# Display_System_sch.net
KiCad netlist of a schematic drawn in Altium Designer
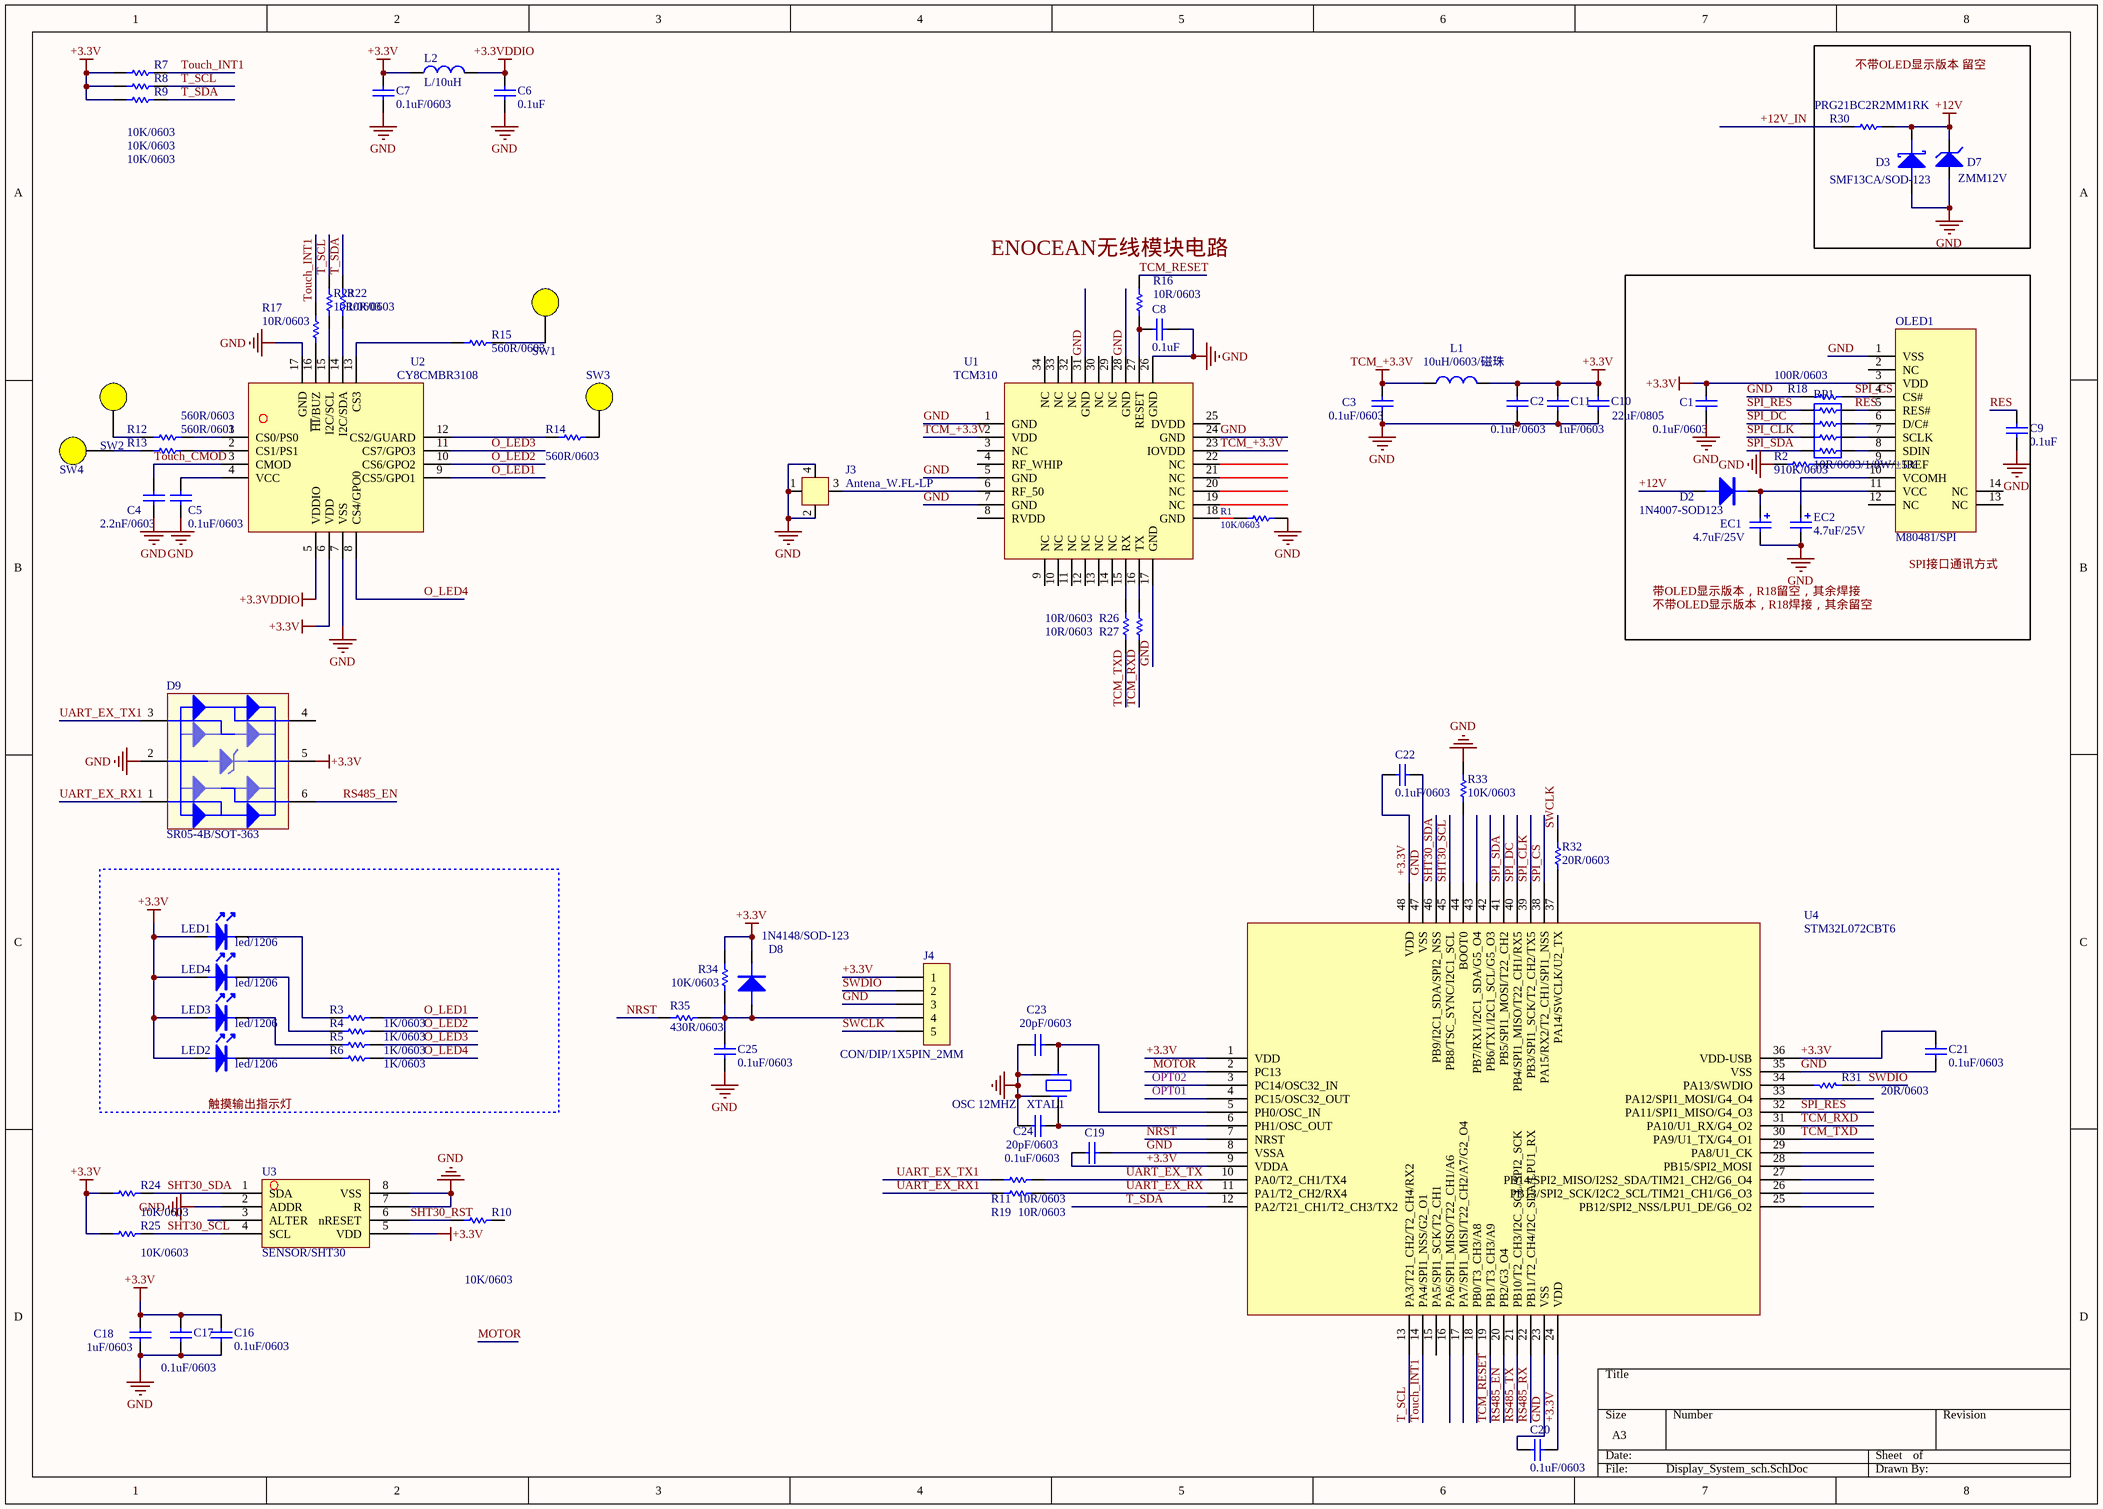
[diagram p0: Display_System_sch.SchDoc]

(export (version "E")
  (design (tool "Eeschema 10.0.6"))
  (components
    (comp (ref "C1")
      (value "0.1uF/0603")
      (footprint "CAP/SMT/0603C")
      (libsource (lib "Menred_原理图 封装库") (part "CAP/CAP/SMT/0603C"))
    )
    (comp (ref "C2")
      (value "0.1uF/0603")
      (footprint "CAP/SMT/0603C")
      (libsource (lib "Menred_原理图 封装库") (part "CAP/CAP/SMT/0603C"))
    )
    (comp (ref "C3")
      (value "0.1uF/0603")
      (footprint "CAP/SMT/0603C")
      (libsource (lib "Menred_原理图 封装库") (part "CAP/CAP/SMT/0603C"))
    )
    (comp (ref "C4")
      (value "2.2nF/0603")
      (footprint "CAP/SMT/0603C")
      (libsource (lib "Menred_原理图 封装库") (part "CAP/CAP/SMT/0603C"))
    )
    (comp (ref "C5")
      (value "0.1uF/0603")
      (footprint "CAP/SMT/0603C")
      (libsource (lib "Menred_原理图 封装库") (part "CAP/CAP/SMT/0603C"))
    )
    (comp (ref "C6")
      (value "0.1uF")
      (footprint "CAP/SMT/0603C")
      (libsource (lib "Menred_原理图 封装库") (part "CAP/CAP/SMT/0603C"))
    )
    (comp (ref "C7")
      (value "0.1uF/0603")
      (footprint "CAP/SMT/0603C")
      (libsource (lib "Menred_原理图 封装库") (part "CAP/CAP/SMT/0603C"))
    )
    (comp (ref "C8")
      (value "0.1uF")
      (footprint "CAP/SMT/0603C")
      (libsource (lib "") (part "CAP/CAP/SMT/0603C_1"))
    )
    (comp (ref "C9")
      (value "0.1uF")
      (footprint "CAP/SMT/0603C")
      (libsource (lib "Menred_原理图 封装库") (part "CAP/CAP/SMT/0603C"))
    )
    (comp (ref "C10")
      (value "22uF/0805")
      (footprint "CAP/SMT/0805C")
      (libsource (lib "Menred_原理图 封装库") (part "CAP/CAP/SMT/0805C"))
    )
    (comp (ref "C11")
      (value "1uF/0603")
      (footprint "CAP/SMT/0603C")
      (libsource (lib "Menred_原理图 封装库") (part "CAP/CAP/SMT/0603C"))
    )
    (comp (ref "C16")
      (value "0.1uF/0603")
      (footprint "CAP/SMT/0603C")
      (libsource (lib "Menred_原理图 封装库") (part "CAP/CAP/SMT/0603C"))
    )
    (comp (ref "C17")
      (value "0.1uF/0603")
      (footprint "CAP/SMT/0603C")
      (libsource (lib "Menred_原理图 封装库") (part "CAP/CAP/SMT/0603C"))
    )
    (comp (ref "C18")
      (value "1uF/0603")
      (footprint "CAP/SMT/0603C")
      (libsource (lib "Menred_原理图 封装库") (part "CAP/CAP/SMT/0603C"))
    )
    (comp (ref "C19")
      (value "0.1uF/0603")
      (footprint "CAP/SMT/0603C")
      (libsource (lib "Menred_原理图 封装库") (part "CAP/CAP/SMT/0603C"))
    )
    (comp (ref "C20")
      (value "0.1uF/0603")
      (footprint "CAP/SMT/0603C")
      (libsource (lib "Menred_原理图 封装库") (part "CAP/CAP/SMT/0603C"))
    )
    (comp (ref "C21")
      (value "0.1uF/0603")
      (footprint "CAP/SMT/0603C")
      (libsource (lib "Menred_原理图 封装库") (part "CAP/CAP/SMT/0603C"))
    )
    (comp (ref "C22")
      (value "0.1uF/0603")
      (footprint "CAP/SMT/0603C")
      (libsource (lib "Menred_原理图 封装库") (part "CAP/CAP/SMT/0603C"))
    )
    (comp (ref "C23")
      (value "20pF/0603")
      (footprint "CAP/SMT/0603C")
      (libsource (lib "Menred_原理图 封装库") (part "CAP/CAP/SMT/0603C"))
    )
    (comp (ref "C24")
      (value "20pF/0603")
      (footprint "CAP/SMT/0603C")
      (libsource (lib "Menred_原理图 封装库") (part "CAP/CAP/SMT/0603C"))
    )
    (comp (ref "C25")
      (value "0.1uF/0603")
      (footprint "CAP/SMT/0603C")
      (libsource (lib "Menred_原理图 封装库") (part "CAP/CAP/SMT/0603C"))
    )
    (comp (ref "D2")
      (value "1N4007-SOD123")
      (footprint "D/SMT/SOD123")
      (libsource (lib "Menred_原理图 封装库") (part "D/D/SMT/1N4007-SOD123"))
    )
    (comp (ref "D3")
      (value "SMF13CA/SOD-123")
      (footprint "D/SMT/SOD123")
      (libsource (lib "Menred_原理图 封装库") (part "D/TVS/SMT/SMF13CA/SOD-123"))
    )
    (comp (ref "D7")
      (value "ZMM12V")
      (footprint "D/SMT/SOD-80")
      (libsource (lib "Menred_原理图 封装库") (part "D/ZENER/SMT/ZMM8V2/SOD80"))
    )
    (comp (ref "D8")
      (value "1N4148/SOD-123")
      (footprint "D/SMT/SOD-123")
      (description "VR=75V T(-65-175)P(0.5W)VF=0.6V")
      (libsource (lib "Menred_原理图 封装库") (part "D/D/SMT/1N4148/SOD-123"))
    )
    (comp (ref "D9")
      (value "SR05-4B/SOT-363")
      (footprint "TSOT-6L")
      (libsource (lib "二极管类器件") (part "D/TVS/SMT/SR05-4B/SOT-363"))
    )
    (comp (ref "EC1")
      (value "4.7uF/25V")
      (footprint "CAP/SMT/TAJA106M010RNJ")
      (libsource (lib "Menred_原理图 封装库") (part "CAP/TEC/SMT/TAJA106M010RNJ"))
    )
    (comp (ref "EC2")
      (value "4.7uF/25V")
      (footprint "CAP/SMT/TAJA106M010RNJ")
      (libsource (lib "Menred_原理图 封装库") (part "CAP/TEC/SMT/TAJA106M010RNJ"))
    )
    (comp (ref "J3")
      (value "Antena_W.FL-LP")
      (footprint "W.FL.LP-3MM")
      (libsource (lib "Menred_原理图 封装库") (part "OTHER/Antena"))
    )
    (comp (ref "J4")
      (value "CON/DIP/1X5PIN_2MM")
      (footprint "CON/DIP/1X5PIN/1.27MM")
      (description "Connector")
      (libsource (lib "Menred_原理图 封装库") (part "CON/DIP/1X5PIN_2MM"))
    )
    (comp (ref "L1")
      (value "10uH/0603/磁珠")
      (footprint "0603R")
      (libsource (lib "JinZhenHui") (part "INDUCTOR1"))
    )
    (comp (ref "L2")
      (value "L/10uH")
      (footprint "L/SMT/0603L")
      (libsource (lib "Menred_原理图 封装库") (part "L/BEAD/SMT/0603L"))
    )
    (comp (ref "LED1")
      (value "led/1206")
      (footprint "D/SMT/LED/1206")
      (libsource (lib "Menred_原理图 封装库") (part "D/LED/SMT/WEJT81GC/1206"))
    )
    (comp (ref "LED2")
      (value "led/1206")
      (footprint "D/SMT/LED/1206")
      (libsource (lib "Menred_原理图 封装库") (part "D/LED/SMT/WEJT81GC/1206"))
    )
    (comp (ref "LED3")
      (value "led/1206")
      (footprint "D/SMT/LED/1206")
      (libsource (lib "Menred_原理图 封装库") (part "D/LED/SMT/WEJT81GC/1206"))
    )
    (comp (ref "LED4")
      (value "led/1206")
      (footprint "D/SMT/LED/1206")
      (libsource (lib "Menred_原理图 封装库") (part "D/LED/SMT/WEJT81GC/1206"))
    )
    (comp (ref "OLED1")
      (value "M80481/SPI")
      (footprint "OLED/M80481/6701")
      (description "OLED/M80481")
      (libsource (lib "Menred_原理图 封装库") (part "OLED/M80481/SPI"))
    )
    (comp (ref "R1")
      (value "10K/0603")
      (footprint "0603R")
      (description "Resistor")
      (fields (field (name "PUBLISHER") "*"))
      (libsource (lib "JinZhenHui") (part "Res"))
    )
    (comp (ref "R2")
      (value "910K/0603")
      (footprint "0603R")
      (libsource (lib "Menred_原理图 封装库") (part "RES/RES/SMT/0603"))
    )
    (comp (ref "R3")
      (value "1K/0603")
      (footprint "0603R")
      (libsource (lib "Menred_原理图 封装库") (part "RES/RES/SMT/0603"))
    )
    (comp (ref "R4")
      (value "1K/0603")
      (footprint "0603R")
      (libsource (lib "Menred_原理图 封装库") (part "RES/RES/SMT/0603"))
    )
    (comp (ref "R5")
      (value "1K/0603")
      (footprint "0603R")
      (libsource (lib "Menred_原理图 封装库") (part "RES/RES/SMT/0603"))
    )
    (comp (ref "R6")
      (value "1K/0603")
      (footprint "0603R")
      (libsource (lib "Menred_原理图 封装库") (part "RES/RES/SMT/0603"))
    )
    (comp (ref "R7")
      (value "10K/0603")
      (footprint "0603R")
      (libsource (lib "Menred_原理图 封装库") (part "RES/RES/SMT/0603"))
    )
    (comp (ref "R8")
      (value "10K/0603")
      (footprint "0603R")
      (libsource (lib "Menred_原理图 封装库") (part "RES/RES/SMT/0603"))
    )
    (comp (ref "R9")
      (value "10K/0603")
      (footprint "0603R")
      (libsource (lib "Menred_原理图 封装库") (part "RES/RES/SMT/0603"))
    )
    (comp (ref "R10")
      (value "10K/0603")
      (footprint "0603R")
      (libsource (lib "Menred_原理图 封装库") (part "RES/RES/SMT/0603"))
    )
    (comp (ref "R11")
      (value "10R/0603")
      (footprint "0603R")
      (libsource (lib "Menred_原理图 封装库") (part "RES/RES/SMT/0603"))
    )
    (comp (ref "R12")
      (value "560R/0603")
      (footprint "0603R")
      (libsource (lib "Menred_原理图 封装库") (part "RES/RES/SMT/0603"))
    )
    (comp (ref "R13")
      (value "560R/0603")
      (footprint "0603R")
      (libsource (lib "Menred_原理图 封装库") (part "RES/RES/SMT/0603"))
    )
    (comp (ref "R14")
      (value "560R/0603")
      (footprint "0603R")
      (libsource (lib "Menred_原理图 封装库") (part "RES/RES/SMT/0603"))
    )
    (comp (ref "R15")
      (value "560R/0603")
      (footprint "0603R")
      (libsource (lib "Menred_原理图 封装库") (part "RES/RES/SMT/0603"))
    )
    (comp (ref "R16")
      (value "10R/0603")
      (footprint "0603R")
      (libsource (lib "Menred_原理图 封装库") (part "RES/RES/SMT/0603"))
    )
    (comp (ref "R17")
      (value "10R/0603")
      (footprint "0603R")
      (libsource (lib "Menred_原理图 封装库") (part "RES/RES/SMT/0603"))
    )
    (comp (ref "R18")
      (value "100R/0603")
      (footprint "0603R")
      (libsource (lib "Menred_原理图 封装库") (part "RES/RES/SMT/0603"))
    )
    (comp (ref "R19")
      (value "10R/0603")
      (footprint "0603R")
      (libsource (lib "Menred_原理图 封装库") (part "RES/RES/SMT/0603"))
    )
    (comp (ref "R22")
      (value "10R/0603")
      (footprint "0603R")
      (libsource (lib "Menred_原理图 封装库") (part "RES/RES/SMT/0603"))
    )
    (comp (ref "R23")
      (value "10R/0603")
      (footprint "0603R")
      (libsource (lib "Menred_原理图 封装库") (part "RES/RES/SMT/0603"))
    )
    (comp (ref "R24")
      (value "10K/0603")
      (footprint "0603R")
      (libsource (lib "Menred_原理图 封装库") (part "RES/RES/SMT/0603"))
    )
    (comp (ref "R25")
      (value "10K/0603")
      (footprint "0603R")
      (libsource (lib "Menred_原理图 封装库") (part "RES/RES/SMT/0603"))
    )
    (comp (ref "R26")
      (value "10R/0603")
      (footprint "0603R")
      (libsource (lib "Menred_原理图 封装库") (part "RES/RES/SMT/0603"))
    )
    (comp (ref "R27")
      (value "10R/0603")
      (footprint "0603R")
      (libsource (lib "Menred_原理图 封装库") (part "RES/RES/SMT/0603"))
    )
    (comp (ref "R30")
      (value "PRG21BC2R2MM1RK")
      (footprint "0805R")
      (libsource (lib "Menred_原理图 封装库") (part "RES/RES/SMT/0805"))
    )
    (comp (ref "R31")
      (value "20R/0603")
      (footprint "0603R")
      (description "Resistor")
      (fields
        (field (name "MANUFACTURER") "Generic Components")
        (field (name "PUBLISHER") "Altium Hobart Technology Centre")
      )
      (libsource (lib "*") (part "Res1"))
    )
    (comp (ref "R32")
      (value "20R/0603")
      (footprint "0603R")
      (description "Resistor")
      (fields
        (field (name "MANUFACTURER") "Generic Components")
        (field (name "PUBLISHER") "Altium Hobart Technology Centre")
      )
      (libsource (lib "*") (part "A_Res_0805"))
    )
    (comp (ref "R33")
      (value "10K/0603")
      (footprint "0603R")
      (libsource (lib "Menred_原理图 封装库") (part "RES/RES/SMT/0603"))
    )
    (comp (ref "R34")
      (value "10K/0603")
      (footprint "0603R")
      (libsource (lib "Menred_原理图 封装库") (part "RES/RES/SMT/0603"))
    )
    (comp (ref "R35")
      (value "430R/0603")
      (footprint "0603R")
      (libsource (lib "Menred_原理图 封装库") (part "RES/RES/SMT/0603"))
    )
    (comp (ref "RP1")
      (value "10R/0603/1/8W/±5%")
      (footprint "0603R*4")
      (description "Isolated Resistor Network")
      (fields (field (name "PUBLISHER") "Altium Limited"))
      (libsource (lib "Menred_原理图 封装库") (part "RES /PACKS/SMT/0603*4"))
    )
    (comp (ref "SW1")
      (value "TOUCH")
      (footprint "SWITCH/TOUCH /四叶草")
      (libsource (lib "Menred_原理图 封装库") (part "SWITCH/TOUCH/SMT/四叶草"))
    )
    (comp (ref "SW2")
      (value "TOUCH")
      (footprint "SWITCH/TOUCH /四叶草")
      (libsource (lib "Menred_原理图 封装库") (part "SWITCH/TOUCH/SMT/四叶草"))
    )
    (comp (ref "SW3")
      (value "TOUCH")
      (footprint "SWITCH/TOUCH /四叶草")
      (libsource (lib "Menred_原理图 封装库") (part "SWITCH/TOUCH/SMT/四叶草"))
    )
    (comp (ref "SW4")
      (value "TOUCH")
      (footprint "SWITCH/TOUCH /四叶草")
      (libsource (lib "Menred_原理图 封装库") (part "SWITCH/TOUCH/SMT/四叶草"))
    )
    (comp (ref "U1") (value "TCM310") (footprint "TCM310") (libsource (lib "Schlib1") (part "TCM_310")))
    (comp (ref "U2")
      (value "CY8CMBR3108")
      (footprint "QFN-16")
      (libsource (lib "集成芯片类") (part "IC/TOUCH/CY8CMBR3108/QFN16"))
    )
    (comp (ref "U3")
      (value "SENSOR/SHT30")
      (footprint "SENSOR/SHT30")
      (description "温湿度传感器")
      (libsource (lib "Menred_原理图 封装库") (part "SENSOR/SHT30"))
    )
    (comp (ref "U4")
      (value "STM32L072CBT6")
      (footprint "TQFP48")
      (libsource (lib "Menred_原理图 封装库") (part "MCU/SMT/STM32L072CBT6/LQFP48"))
    )
    (comp (ref "XTAL1")
      (value "OSC 12MHZ")
      (footprint "OSC/SMT/12M")
      (libsource (lib "Menred_原理图 封装库") (part "XTAL/SMT/OSC12MHZ-2"))
    )
  )
  (nets
    (net (code "1") (name "+3.3V") (class "Default")
      (node (ref "C1") (pin "2") (pinfunction "2_2") (pintype "passive"))
      (node (ref "C10") (pin "1") (pinfunction "1_1") (pintype "passive"))
      (node (ref "C11") (pin "2") (pinfunction "2_2") (pintype "passive"))
      (node (ref "C16") (pin "1") (pinfunction "1_1") (pintype "passive"))
      (node (ref "C17") (pin "2") (pinfunction "2_2") (pintype "passive"))
      (node (ref "C18") (pin "2") (pinfunction "2_2") (pintype "passive"))
      (node (ref "C19") (pin "2") (pinfunction "2_2") (pintype "passive"))
      (node (ref "C2") (pin "2") (pinfunction "2_2") (pintype "passive"))
      (node (ref "C20") (pin "1") (pinfunction "1_1") (pintype "passive"))
      (node (ref "C21") (pin "2") (pinfunction "2_2") (pintype "passive"))
      (node (ref "C22") (pin "2") (pinfunction "2_2") (pintype "passive"))
      (node (ref "C7") (pin "2") (pinfunction "2_2") (pintype "passive"))
      (node (ref "D8") (pin "1") (pinfunction "K_1") (pintype "passive"))
      (node (ref "D9") (pin "5") (pintype "passive"))
      (node (ref "J4") (pin "1") (pinfunction "1_1") (pintype "passive"))
      (node (ref "L1") (pin "1") (pinfunction "1_1") (pintype "passive"))
      (node (ref "L2") (pin "1") (pinfunction "1_1") (pintype "passive"))
      (node (ref "LED1") (pin "2") (pinfunction "A_2") (pintype "passive"))
      (node (ref "LED2") (pin "2") (pinfunction "A_2") (pintype "passive"))
      (node (ref "LED3") (pin "2") (pinfunction "A_2") (pintype "passive"))
      (node (ref "LED4") (pin "2") (pinfunction "A_2") (pintype "passive"))
      (node (ref "OLED1") (pin "3") (pinfunction "VDD_3") (pintype "passive"))
      (node (ref "R24") (pin "1") (pinfunction "1_1") (pintype "passive"))
      (node (ref "R25") (pin "1") (pinfunction "1_1") (pintype "passive"))
      (node (ref "R34") (pin "2") (pinfunction "2_2") (pintype "passive"))
      (node (ref "R7") (pin "1") (pinfunction "1_1") (pintype "passive"))
      (node (ref "R8") (pin "1") (pinfunction "1_1") (pintype "passive"))
      (node (ref "R9") (pin "1") (pinfunction "1_1") (pintype "passive"))
      (node (ref "U2") (pin "6") (pinfunction "VDD_6") (pintype "passive"))
      (node (ref "U3") (pin "5") (pinfunction "VDD_5") (pintype "passive"))
      (node (ref "U4") (pin "1") (pinfunction "VDD_1") (pintype "power_in"))
      (node (ref "U4") (pin "24") (pinfunction "VDD_24") (pintype "passive"))
      (node (ref "U4") (pin "36") (pinfunction "VDD-USB_36") (pintype "passive"))
      (node (ref "U4") (pin "48") (pinfunction "VDD_48") (pintype "passive"))
      (node (ref "U4") (pin "9") (pinfunction "VDDA_9") (pintype "power_in"))
    )
    (net (code "2") (name "+3.3VDDIO") (class "Default")
      (node (ref "C6") (pin "2") (pinfunction "2_2") (pintype "passive"))
      (node (ref "L2") (pin "2") (pinfunction "2_2") (pintype "passive"))
      (node (ref "U2") (pin "5") (pinfunction "VDDIO_5") (pintype "passive"))
    )
    (net (code "3") (name "+12V") (class "Default")
      (node (ref "D2") (pin "2") (pinfunction "A_2") (pintype "passive"))
      (node (ref "D3") (pin "1") (pinfunction "A_1") (pintype "passive"))
      (node (ref "D7") (pin "1") (pinfunction "K_1") (pintype "passive"))
      (node (ref "R30") (pin "2") (pinfunction "2_2") (pintype "passive"))
    )
    (net (code "4") (name "/+12V_IN") (class "Default")
      (node (ref "R30") (pin "1") (pinfunction "1_1") (pintype "passive"))
    )
    (net (code "6") (name "/MOTOR") (class "Default")
      (node (ref "U4") (pin "2") (pinfunction "PC13_2") (pintype "power_in"))
    )
    (net (code "7") (name "/NRST") (class "Default")
      (node (ref "R35") (pin "2") (pinfunction "2_2") (pintype "passive"))
      (node (ref "U4") (pin "7") (pinfunction "NRST_7") (pintype "power_in"))
    )
    (net (code "8") (name "/OPT01") (class "Default")
      (node (ref "U4") (pin "4") (pinfunction "PC15/OSC32_OUT_4") (pintype "power_in"))
    )
    (net (code "9") (name "/OPT02") (class "Default")
      (node (ref "U4") (pin "3") (pinfunction "PC14/OSC32_IN_3") (pintype "power_in"))
    )
    (net (code "10") (name "/O_LED1") (class "Default")
      (node (ref "R3") (pin "1") (pinfunction "1_1") (pintype "passive"))
      (node (ref "U2") (pin "9") (pinfunction "CS5/GPO1_9") (pintype "passive"))
    )
    (net (code "11") (name "/O_LED2") (class "Default")
      (node (ref "R4") (pin "1") (pinfunction "1_1") (pintype "passive"))
      (node (ref "U2") (pin "10") (pinfunction "CS6/GPO2_10") (pintype "passive"))
    )
    (net (code "12") (name "/O_LED3") (class "Default")
      (node (ref "R5") (pin "1") (pinfunction "1_1") (pintype "passive"))
      (node (ref "U2") (pin "11") (pinfunction "CS7/GPO3_11") (pintype "passive"))
    )
    (net (code "13") (name "/O_LED4") (class "Default")
      (node (ref "R6") (pin "1") (pinfunction "1_1") (pintype "passive"))
      (node (ref "U2") (pin "8") (pinfunction "CS4/GPO0_8") (pintype "passive"))
    )
    (net (code "14") (name "/RES") (class "Default")
      (node (ref "C9") (pin "1") (pinfunction "1_1") (pintype "passive"))
      (node (ref "OLED1") (pin "5") (pinfunction "RES#_5") (pintype "passive"))
      (node (ref "RP1") (pin "4") (pinfunction "4_4") (pintype "passive"))
    )
    (net (code "15") (name "/RS485_EN") (class "Default")
      (node (ref "D9") (pin "6") (pintype "passive"))
      (node (ref "U4") (pin "20") (pinfunction "PB2/G3_O4_20") (pintype "passive"))
    )
    (net (code "16") (name "/RS485_RX") (class "Default")
      (node (ref "U4") (pin "22") (pinfunction "PB11/T2_CH4/I2C_SDA/LPU1_RX_22") (pintype "passive"))
    )
    (net (code "17") (name "/RS485_TX") (class "Default")
      (node (ref "U4") (pin "21") (pinfunction "PB10/T2_CH3/I2C_SCL/SPI2_SCK_21") (pintype "passive"))
    )
    (net (code "18") (name "/SHT30_RST") (class "Default")
      (node (ref "R10") (pin "1") (pinfunction "1_1") (pintype "passive"))
      (node (ref "U3") (pin "6") (pinfunction "nRESET_6") (pintype "passive"))
    )
    (net (code "19") (name "/SHT30_SCL") (class "Default")
      (node (ref "R25") (pin "2") (pinfunction "2_2") (pintype "passive"))
      (node (ref "U3") (pin "4") (pinfunction "SCL_4") (pintype "passive"))
      (node (ref "U4") (pin "45") (pinfunction "PB8/TSC_SYNC/I2C1_SCL_45") (pintype "passive"))
    )
    (net (code "20") (name "/SHT30_SDA") (class "Default")
      (node (ref "R24") (pin "2") (pinfunction "2_2") (pintype "passive"))
      (node (ref "U3") (pin "1") (pinfunction "SDA_1") (pintype "passive"))
      (node (ref "U4") (pin "46") (pinfunction "PB9/I2C1_SDA/SPI2_NSS_46") (pintype "passive"))
    )
    (net (code "21") (name "/SPI_CLK") (class "Default")
      (node (ref "RP1") (pin "7") (pinfunction "7_7") (pintype "passive"))
      (node (ref "U4") (pin "39") (pinfunction "PB3/SPI1_SCK/T2_CH2/TX5_39") (pintype "passive"))
    )
    (net (code "22") (name "/SPI_CS") (class "Default")
      (node (ref "OLED1") (pin "4") (pinfunction "CS#_4") (pintype "passive"))
      (node (ref "R18") (pin "2") (pinfunction "2_2") (pintype "passive"))
      (node (ref "U4") (pin "38") (pinfunction "PA15/RX2/T2_CH1/SPI1_NSS_38") (pintype "passive"))
    )
    (net (code "23") (name "/SPI_DC") (class "Default")
      (node (ref "RP1") (pin "6") (pinfunction "6_6") (pintype "passive"))
      (node (ref "U4") (pin "40") (pinfunction "PB4/SPI1_MISO/T22_CH1/RX5_40") (pintype "passive"))
    )
    (net (code "24") (name "/SPI_RES") (class "Default")
      (node (ref "RP1") (pin "5") (pinfunction "5_5") (pintype "passive"))
      (node (ref "U4") (pin "32") (pinfunction "PA11/SPI1_MISO/G4_O3_32") (pintype "passive"))
    )
    (net (code "25") (name "/SPI_SDA") (class "Default")
      (node (ref "RP1") (pin "8") (pinfunction "8_8") (pintype "passive"))
      (node (ref "U4") (pin "41") (pinfunction "PB5/SPI1_MOSI/T22_CH2_41") (pintype "passive"))
    )
    (net (code "27") (name "/SWCLK") (class "Default")
      (node (ref "J4") (pin "5") (pinfunction "5_5") (pintype "passive"))
      (node (ref "R32") (pin "2") (pinfunction "2_2") (pintype "passive"))
    )
    (net (code "28") (name "/SWDIO") (class "Default")
      (node (ref "J4") (pin "2") (pinfunction "2_2") (pintype "passive"))
      (node (ref "R31") (pin "1") (pinfunction "1_1") (pintype "passive"))
    )
    (net (code "29") (name "/TCM_RESET") (class "Default")
      (node (ref "R16") (pin "2") (pinfunction "2_2") (pintype "passive"))
      (node (ref "U4") (pin "19") (pinfunction "PB1/T3_CH3/A9_19") (pintype "passive"))
    )
    (net (code "30") (name "/TCM_RXD") (class "Default")
      (node (ref "R27") (pin "1") (pinfunction "1_1") (pintype "passive"))
      (node (ref "U4") (pin "31") (pinfunction "PA10/U1_RX/G4_O2_31") (pintype "passive"))
    )
    (net (code "31") (name "/TCM_TXD") (class "Default")
      (node (ref "R26") (pin "1") (pinfunction "1_1") (pintype "passive"))
      (node (ref "U4") (pin "30") (pinfunction "PA9/U1_TX/G4_O1_30") (pintype "passive"))
    )
    (net (code "32") (name "/T_SCL") (class "Default")
      (node (ref "R23") (pin "1") (pinfunction "1_1") (pintype "passive"))
      (node (ref "R8") (pin "2") (pinfunction "2_2") (pintype "passive"))
      (node (ref "U4") (pin "13") (pinfunction "PA3/T21_CH2/T2_CH4/RX2_13") (pintype "passive"))
    )
    (net (code "33") (name "/T_SDA") (class "Default")
      (node (ref "R22") (pin "1") (pinfunction "1_1") (pintype "passive"))
      (node (ref "R9") (pin "2") (pinfunction "2_2") (pintype "passive"))
      (node (ref "U4") (pin "12") (pinfunction "PA2/T21_CH1/T2_CH3/TX2_12") (pintype "passive"))
    )
    (net (code "34") (name "/Touch_CMOD") (class "Default")
      (node (ref "C4") (pin "2") (pinfunction "2_2") (pintype "passive"))
      (node (ref "U2") (pin "3") (pinfunction "CMOD_3") (pintype "passive"))
    )
    (net (code "35") (name "/Touch_INT1") (class "Default")
      (node (ref "R17") (pin "2") (pinfunction "2_2") (pintype "passive"))
      (node (ref "R7") (pin "2") (pinfunction "2_2") (pintype "passive"))
      (node (ref "U4") (pin "14") (pinfunction "PA4/SPI1_NSS/G2_O1_14") (pintype "passive"))
    )
    (net (code "36") (name "/UART_EX_RX") (class "Default")
      (node (ref "R19") (pin "1") (pinfunction "1_1") (pintype "passive"))
      (node (ref "U4") (pin "11") (pinfunction "PA1/T2_CH2/RX4_11") (pintype "power_in"))
    )
    (net (code "37") (name "/UART_EX_RX1") (class "Default")
      (node (ref "D9") (pin "1") (pintype "passive"))
      (node (ref "R19") (pin "2") (pinfunction "2_2") (pintype "passive"))
    )
    (net (code "38") (name "/UART_EX_TX") (class "Default")
      (node (ref "R11") (pin "1") (pinfunction "1_1") (pintype "passive"))
      (node (ref "U4") (pin "10") (pinfunction "PA0/T2_CH1/TX4_10") (pintype "power_in"))
    )
    (net (code "39") (name "/UART_EX_TX1") (class "Default")
      (node (ref "D9") (pin "3") (pintype "passive"))
      (node (ref "R11") (pin "2") (pinfunction "2_2") (pintype "passive"))
    )
    (net (code "44") (name "GND") (class "Default")
      (node (ref "C1") (pin "1") (pinfunction "1_1") (pintype "passive"))
      (node (ref "C10") (pin "2") (pinfunction "2_2") (pintype "passive"))
      (node (ref "C11") (pin "1") (pinfunction "1_1") (pintype "passive"))
      (node (ref "C16") (pin "2") (pinfunction "2_2") (pintype "passive"))
      (node (ref "C17") (pin "1") (pinfunction "1_1") (pintype "passive"))
      (node (ref "C18") (pin "1") (pinfunction "1_1") (pintype "passive"))
      (node (ref "C19") (pin "1") (pinfunction "1_1") (pintype "passive"))
      (node (ref "C2") (pin "1") (pinfunction "1_1") (pintype "passive"))
      (node (ref "C20") (pin "2") (pinfunction "2_2") (pintype "passive"))
      (node (ref "C21") (pin "1") (pinfunction "1_1") (pintype "passive"))
      (node (ref "C22") (pin "1") (pinfunction "1_1") (pintype "passive"))
      (node (ref "C23") (pin "2") (pinfunction "2_2") (pintype "passive"))
      (node (ref "C24") (pin "2") (pinfunction "2_2") (pintype "passive"))
      (node (ref "C25") (pin "1") (pinfunction "1_1") (pintype "passive"))
      (node (ref "C3") (pin "1") (pinfunction "1_1") (pintype "passive"))
      (node (ref "C4") (pin "1") (pinfunction "1_1") (pintype "passive"))
      (node (ref "C5") (pin "1") (pinfunction "1_1") (pintype "passive"))
      (node (ref "C6") (pin "1") (pinfunction "1_1") (pintype "passive"))
      (node (ref "C7") (pin "1") (pinfunction "1_1") (pintype "passive"))
      (node (ref "C8") (pin "1") (pinfunction "1_1") (pintype "passive"))
      (node (ref "C9") (pin "2") (pinfunction "2_2") (pintype "passive"))
      (node (ref "D3") (pin "2") (pinfunction "K_2") (pintype "passive"))
      (node (ref "D7") (pin "2") (pinfunction "A_2") (pintype "passive"))
      (node (ref "D9") (pin "2") (pintype "passive"))
      (node (ref "EC1") (pin "2") (pinfunction "2_2") (pintype "passive"))
      (node (ref "EC2") (pin "2") (pinfunction "2_2") (pintype "passive"))
      (node (ref "J3") (pin "1") (pinfunction "NC_1") (pintype "passive"))
      (node (ref "J3") (pin "2") (pinfunction "NC_2") (pintype "passive"))
      (node (ref "J3") (pin "4") (pinfunction "NC_4") (pintype "passive"))
      (node (ref "J4") (pin "3") (pinfunction "3_3") (pintype "passive"))
      (node (ref "OLED1") (pin "1") (pinfunction "VSS_1") (pintype "passive"))
      (node (ref "R1") (pin "1") (pinfunction "1_1") (pintype "passive"))
      (node (ref "R18") (pin "1") (pinfunction "1_1") (pintype "passive"))
      (node (ref "R2") (pin "1") (pinfunction "1_1") (pintype "passive"))
      (node (ref "R33") (pin "1") (pinfunction "1_1") (pintype "passive"))
      (node (ref "U1") (pin "1") (pinfunction "GND_1") (pintype "passive"))
      (node (ref "U1") (pin "17") (pinfunction "GND_17") (pintype "passive"))
      (node (ref "U1") (pin "24") (pinfunction "GND_24") (pintype "passive"))
      (node (ref "U1") (pin "26") (pinfunction "GND_26") (pintype "passive"))
      (node (ref "U1") (pin "28") (pinfunction "GND_28") (pintype "passive"))
      (node (ref "U1") (pin "31") (pinfunction "GND_31") (pintype "passive"))
      (node (ref "U1") (pin "5") (pinfunction "GND_5") (pintype "passive"))
      (node (ref "U1") (pin "7") (pinfunction "GND_7") (pintype "passive"))
      (node (ref "U2") (pin "17") (pinfunction "GND_17") (pintype "passive"))
      (node (ref "U2") (pin "7") (pinfunction "VSS_7") (pintype "passive"))
      (node (ref "U3") (pin "2") (pinfunction "ADDR_2") (pintype "passive"))
      (node (ref "U3") (pin "7") (pinfunction "R_7") (pintype "passive"))
      (node (ref "U3") (pin "8") (pinfunction "VSS_8") (pintype "passive"))
      (node (ref "U4") (pin "23") (pinfunction "VSS_23") (pintype "passive"))
      (node (ref "U4") (pin "35") (pinfunction "VSS_35") (pintype "passive"))
      (node (ref "U4") (pin "47") (pinfunction "VSS_47") (pintype "passive"))
      (node (ref "U4") (pin "8") (pinfunction "VSSA_8") (pintype "power_in"))
      (node (ref "XTAL1") (pin "2") (pinfunction "2_2") (pintype "passive"))
      (node (ref "XTAL1") (pin "4") (pinfunction "4_4") (pintype "passive"))
    )
    (net (code "45") (name "Net-(D2-K)") (class "Default")
      (node (ref "D2") (pin "1") (pinfunction "K_1") (pintype "passive"))
      (node (ref "EC1") (pin "1") (pinfunction "1_1") (pintype "passive"))
      (node (ref "OLED1") (pin "11") (pinfunction "VCC_11") (pintype "passive"))
    )
    (net (code "46") (name "Net-(D8-A)") (class "Default")
      (node (ref "C25") (pin "2") (pinfunction "2_2") (pintype "passive"))
      (node (ref "D8") (pin "2") (pinfunction "A_2") (pintype "passive"))
      (node (ref "J4") (pin "4") (pinfunction "4_4") (pintype "passive"))
      (node (ref "R34") (pin "1") (pinfunction "1_1") (pintype "passive"))
      (node (ref "R35") (pin "1") (pinfunction "1_1") (pintype "passive"))
    )
    (net (code "47") (name "Net-(LED1-K)") (class "Default")
      (node (ref "LED1") (pin "1") (pinfunction "K_1") (pintype "passive"))
      (node (ref "R3") (pin "2") (pinfunction "2_2") (pintype "passive"))
    )
    (net (code "48") (name "Net-(LED2-K)") (class "Default")
      (node (ref "LED2") (pin "1") (pinfunction "K_1") (pintype "passive"))
      (node (ref "R6") (pin "2") (pinfunction "2_2") (pintype "passive"))
    )
    (net (code "49") (name "Net-(LED3-K)") (class "Default")
      (node (ref "LED3") (pin "1") (pinfunction "K_1") (pintype "passive"))
      (node (ref "R5") (pin "2") (pinfunction "2_2") (pintype "passive"))
    )
    (net (code "50") (name "Net-(LED4-K)") (class "Default")
      (node (ref "LED4") (pin "1") (pinfunction "K_1") (pintype "passive"))
      (node (ref "R4") (pin "2") (pinfunction "2_2") (pintype "passive"))
    )
    (net (code "51") (name "Net-(OLED1-D{slash}C#)") (class "Default")
      (node (ref "OLED1") (pin "6") (pinfunction "D/C#_6") (pintype "passive"))
      (node (ref "RP1") (pin "3") (pinfunction "3_3") (pintype "passive"))
    )
    (net (code "52") (name "Net-(OLED1-IREF)") (class "Default")
      (node (ref "OLED1") (pin "9") (pinfunction "IREF_9") (pintype "passive"))
      (node (ref "R2") (pin "2") (pinfunction "2_2") (pintype "passive"))
    )
    (net (code "53") (name "Net-(OLED1-SCLK)") (class "Default")
      (node (ref "OLED1") (pin "7") (pinfunction "SCLK_7") (pintype "passive"))
      (node (ref "RP1") (pin "2") (pinfunction "2_2") (pintype "passive"))
    )
    (net (code "54") (name "Net-(OLED1-SDIN)") (class "Default")
      (node (ref "OLED1") (pin "8") (pinfunction "SDIN_8") (pintype "passive"))
      (node (ref "RP1") (pin "1") (pinfunction "1_1") (pintype "passive"))
    )
    (net (code "55") (name "Net-(OLED1-VCOMH)") (class "Default")
      (node (ref "EC2") (pin "1") (pinfunction "1_1") (pintype "passive"))
      (node (ref "OLED1") (pin "10") (pinfunction "VCOMH_10") (pintype "passive"))
    )
    (net (code "56") (name "Net-(R1-Pad2)") (class "Default")
      (node (ref "R1") (pin "2") (pinfunction "2_2") (pintype "passive"))
      (node (ref "U1") (pin "18") (pinfunction "GND_18") (pintype "passive"))
    )
    (net (code "57") (name "Net-(R12-Pad1)") (class "Default")
      (node (ref "R12") (pin "1") (pinfunction "1_1") (pintype "passive"))
      (node (ref "SW2") (pin "1") (pinfunction "1_1") (pintype "passive"))
    )
    (net (code "58") (name "Net-(R13-Pad1)") (class "Default")
      (node (ref "R13") (pin "1") (pinfunction "1_1") (pintype "passive"))
      (node (ref "SW4") (pin "1") (pinfunction "1_1") (pintype "passive"))
    )
    (net (code "59") (name "Net-(R14-Pad2)") (class "Default")
      (node (ref "R14") (pin "2") (pinfunction "2_2") (pintype "passive"))
      (node (ref "SW3") (pin "1") (pinfunction "1_1") (pintype "passive"))
    )
    (net (code "60") (name "Net-(R15-Pad2)") (class "Default")
      (node (ref "R15") (pin "2") (pinfunction "2_2") (pintype "passive"))
      (node (ref "SW1") (pin "1") (pinfunction "1_1") (pintype "passive"))
    )
    (net (code "61") (name "Net-(U1-RESET)") (class "Default")
      (node (ref "C8") (pin "2") (pinfunction "2_2") (pintype "passive"))
      (node (ref "R16") (pin "1") (pinfunction "1_1") (pintype "passive"))
      (node (ref "U1") (pin "27") (pinfunction "RESET_27") (pintype "passive"))
    )
    (net (code "62") (name "Net-(U1-RF_50)") (class "Default")
      (node (ref "J3") (pin "3") (pinfunction "NC_3") (pintype "passive"))
      (node (ref "U1") (pin "6") (pinfunction "RF_50_6") (pintype "passive"))
    )
    (net (code "63") (name "Net-(U1-RX)") (class "Default")
      (node (ref "R26") (pin "2") (pinfunction "2_2") (pintype "passive"))
      (node (ref "U1") (pin "15") (pinfunction "RX_15") (pintype "passive"))
    )
    (net (code "64") (name "Net-(U1-TX)") (class "Default")
      (node (ref "R27") (pin "2") (pinfunction "2_2") (pintype "passive"))
      (node (ref "U1") (pin "16") (pinfunction "TX_16") (pintype "passive"))
    )
    (net (code "65") (name "Net-(U2-CS0{slash}PS0)") (class "Default")
      (node (ref "R12") (pin "2") (pinfunction "2_2") (pintype "passive"))
      (node (ref "U2") (pin "1") (pinfunction "CS0/PS0_1") (pintype "passive"))
    )
    (net (code "66") (name "Net-(U2-CS1{slash}PS1)") (class "Default")
      (node (ref "R13") (pin "2") (pinfunction "2_2") (pintype "passive"))
      (node (ref "U2") (pin "2") (pinfunction "CS1/PS1_2") (pintype "passive"))
    )
    (net (code "67") (name "Net-(U2-CS2{slash}GUARD)") (class "Default")
      (node (ref "R14") (pin "1") (pinfunction "1_1") (pintype "passive"))
      (node (ref "U2") (pin "12") (pinfunction "CS2/GUARD_12") (pintype "passive"))
    )
    (net (code "68") (name "Net-(U2-CS3)") (class "Default")
      (node (ref "R15") (pin "1") (pinfunction "1_1") (pintype "passive"))
      (node (ref "U2") (pin "13") (pinfunction "CS3_13") (pintype "passive"))
    )
    (net (code "69") (name "Net-(U2-I2C{slash}SCL)") (class "Default")
      (node (ref "R23") (pin "2") (pinfunction "2_2") (pintype "passive"))
      (node (ref "U2") (pin "15") (pinfunction "I2C/SCL_15") (pintype "passive"))
    )
    (net (code "70") (name "Net-(U2-I2C{slash}SDA)") (class "Default")
      (node (ref "R22") (pin "2") (pinfunction "2_2") (pintype "passive"))
      (node (ref "U2") (pin "14") (pinfunction "I2C/SDA_14") (pintype "passive"))
    )
    (net (code "71") (name "Net-(U2-VCC)") (class "Default")
      (node (ref "C5") (pin "2") (pinfunction "2_2") (pintype "passive"))
      (node (ref "U2") (pin "4") (pinfunction "VCC_4") (pintype "passive"))
    )
    (net (code "72") (name "Net-(U2-~{HI}{slash}BUZ)") (class "Default")
      (node (ref "R17") (pin "1") (pinfunction "1_1") (pintype "passive"))
      (node (ref "U2") (pin "16") (pinfunction "~{HI}/BUZ_16") (pintype "passive"))
    )
    (net (code "73") (name "Net-(U4-BOOT0)") (class "Default")
      (node (ref "R33") (pin "2") (pinfunction "2_2") (pintype "passive"))
      (node (ref "U4") (pin "44") (pinfunction "BOOT0_44") (pintype "passive"))
    )
    (net (code "74") (name "Net-(U4-PA13{slash}SWDIO)") (class "Default")
      (node (ref "R31") (pin "2") (pinfunction "2_2") (pintype "passive"))
      (node (ref "U4") (pin "34") (pinfunction "PA13/SWDIO_34") (pintype "passive"))
    )
    (net (code "75") (name "Net-(U4-PA14{slash}SWCLK{slash}U2_TX)") (class "Default")
      (node (ref "R32") (pin "1") (pinfunction "1_1") (pintype "passive"))
      (node (ref "U4") (pin "37") (pinfunction "PA14/SWCLK/U2_TX_37") (pintype "passive"))
    )
    (net (code "76") (name "Net-(U4-PH0{slash}OSC_IN)") (class "Default")
      (node (ref "C23") (pin "1") (pinfunction "1_1") (pintype "passive"))
      (node (ref "U4") (pin "5") (pinfunction "PH0/OSC_IN_5") (pintype "power_in"))
      (node (ref "XTAL1") (pin "3") (pinfunction "3_3") (pintype "passive"))
    )
    (net (code "77") (name "Net-(U4-PH1{slash}OSC_OUT)") (class "Default")
      (node (ref "C24") (pin "1") (pinfunction "1_1") (pintype "passive"))
      (node (ref "U4") (pin "6") (pinfunction "PH1/OSC_OUT_6") (pintype "power_in"))
      (node (ref "XTAL1") (pin "1") (pinfunction "1_1") (pintype "passive"))
    )
    (net (code "78") (name "TCM_+3.3V") (class "Default")
      (node (ref "C3") (pin "2") (pinfunction "2_2") (pintype "passive"))
      (node (ref "L1") (pin "2") (pinfunction "2_2") (pintype "passive"))
      (node (ref "U1") (pin "2") (pinfunction "VDD_2") (pintype "passive"))
      (node (ref "U1") (pin "23") (pinfunction "IOVDD_23") (pintype "passive"))
    )
    (net (code "79") (name "unconnected-(D9-Pad4)") (class "Default")
      (node (ref "D9") (pin "4") (pintype "passive"))
    )
    (net (code "80") (name "unconnected-(OLED1-NC-Pad2)") (class "Default")
      (node (ref "OLED1") (pin "2") (pinfunction "NC_2") (pintype "passive"))
    )
    (net (code "81") (name "unconnected-(OLED1-NC-Pad12)") (class "Default")
      (node (ref "OLED1") (pin "12") (pinfunction "NC_12") (pintype "passive"))
    )
    (net (code "82") (name "unconnected-(OLED1-NC-Pad13)") (class "Default")
      (node (ref "OLED1") (pin "13") (pinfunction "NC_13") (pintype "passive"))
    )
    (net (code "83") (name "unconnected-(OLED1-NC-Pad14)") (class "Default")
      (node (ref "OLED1") (pin "14") (pinfunction "NC_14") (pintype "passive"))
    )
    (net (code "84") (name "unconnected-(R10-Pad2)") (class "Default")
      (node (ref "R10") (pin "2") (pinfunction "2_2") (pintype "passive"))
    )
    (net (code "85") (name "unconnected-(U1-DVDD-Pad25)") (class "Default")
      (node (ref "U1") (pin "25") (pinfunction "DVDD_25") (pintype "passive"))
    )
    (net (code "86") (name "unconnected-(U1-NC-Pad3)") (class "Default")
      (node (ref "U1") (pin "3") (pinfunction "NC_3") (pintype "passive"))
    )
    (net (code "87") (name "unconnected-(U1-NC-Pad9)") (class "Default")
      (node (ref "U1") (pin "9") (pinfunction "NC_9") (pintype "passive"))
    )
    (net (code "88") (name "unconnected-(U1-NC-Pad10)") (class "Default")
      (node (ref "U1") (pin "10") (pinfunction "NC_10") (pintype "passive"))
    )
    (net (code "89") (name "unconnected-(U1-NC-Pad11)") (class "Default")
      (node (ref "U1") (pin "11") (pinfunction "NC_11") (pintype "passive"))
    )
    (net (code "90") (name "unconnected-(U1-NC-Pad12)") (class "Default")
      (node (ref "U1") (pin "12") (pinfunction "NC_12") (pintype "passive"))
    )
    (net (code "91") (name "unconnected-(U1-NC-Pad13)") (class "Default")
      (node (ref "U1") (pin "13") (pinfunction "NC_13") (pintype "passive"))
    )
    (net (code "92") (name "unconnected-(U1-NC-Pad14)") (class "Default")
      (node (ref "U1") (pin "14") (pinfunction "NC_14") (pintype "passive"))
    )
    (net (code "93") (name "unconnected-(U1-NC-Pad19)") (class "Default")
      (node (ref "U1") (pin "19") (pinfunction "NC_19") (pintype "passive"))
    )
    (net (code "94") (name "unconnected-(U1-NC-Pad20)") (class "Default")
      (node (ref "U1") (pin "20") (pinfunction "NC_20") (pintype "passive"))
    )
    (net (code "95") (name "unconnected-(U1-NC-Pad21)") (class "Default")
      (node (ref "U1") (pin "21") (pinfunction "NC_21") (pintype "passive"))
    )
    (net (code "96") (name "unconnected-(U1-NC-Pad22)") (class "Default")
      (node (ref "U1") (pin "22") (pinfunction "NC_22") (pintype "passive"))
    )
    (net (code "97") (name "unconnected-(U1-NC-Pad29)") (class "Default")
      (node (ref "U1") (pin "29") (pinfunction "NC_29") (pintype "passive"))
    )
    (net (code "98") (name "unconnected-(U1-NC-Pad30)") (class "Default")
      (node (ref "U1") (pin "30") (pinfunction "NC_30") (pintype "passive"))
    )
    (net (code "99") (name "unconnected-(U1-NC-Pad32)") (class "Default")
      (node (ref "U1") (pin "32") (pinfunction "NC_32") (pintype "passive"))
    )
    (net (code "100") (name "unconnected-(U1-NC-Pad33)") (class "Default")
      (node (ref "U1") (pin "33") (pinfunction "NC_33") (pintype "passive"))
    )
    (net (code "101") (name "unconnected-(U1-NC-Pad34)") (class "Default")
      (node (ref "U1") (pin "34") (pinfunction "NC_34") (pintype "passive"))
    )
    (net (code "102") (name "unconnected-(U1-RF_WHIP-Pad4)") (class "Default")
      (node (ref "U1") (pin "4") (pinfunction "RF_WHIP_4") (pintype "passive"))
    )
    (net (code "103") (name "unconnected-(U1-RVDD-Pad8)") (class "Default")
      (node (ref "U1") (pin "8") (pinfunction "RVDD_8") (pintype "passive"))
    )
    (net (code "104") (name "unconnected-(U3-ALTER-Pad3)") (class "Default")
      (node (ref "U3") (pin "3") (pinfunction "ALTER_3") (pintype "passive"))
    )
    (net (code "105") (name "unconnected-(U4-PA5{slash}SPI1_SCK{slash}T2_CH1-Pad15)") (class "Default")
      (node (ref "U4") (pin "15") (pinfunction "PA5/SPI1_SCK/T2_CH1_15") (pintype "passive"))
    )
    (net (code "106") (name "unconnected-(U4-PA6{slash}SPI1_MISO{slash}T22_CH1{slash}A6-Pad16)") (class "Default")
      (node (ref "U4") (pin "16") (pinfunction "PA6/SPI1_MISO/T22_CH1/A6_16") (pintype "passive"))
    )
    (net (code "107") (name "unconnected-(U4-PA7{slash}SPI1_MISI{slash}T22_CH2{slash}A7{slash}G2_O4-Pad17)") (class "Default")
      (node (ref "U4") (pin "17") (pinfunction "PA7/SPI1_MISI/T22_CH2/A7/G2_O4_17") (pintype "passive"))
    )
    (net (code "108") (name "unconnected-(U4-PA8{slash}U1_CK-Pad29)") (class "Default")
      (node (ref "U4") (pin "29") (pinfunction "PA8/U1_CK_29") (pintype "passive"))
    )
    (net (code "109") (name "unconnected-(U4-PA12{slash}SPI1_MOSI{slash}G4_O4-Pad33)") (class "Default")
      (node (ref "U4") (pin "33") (pinfunction "PA12/SPI1_MOSI/G4_O4_33") (pintype "passive"))
    )
    (net (code "110") (name "unconnected-(U4-PB0{slash}T3_CH3{slash}A8-Pad18)") (class "Default")
      (node (ref "U4") (pin "18") (pinfunction "PB0/T3_CH3/A8_18") (pintype "passive"))
    )
    (net (code "111") (name "unconnected-(U4-PB6{slash}TX1{slash}I2C1_SCL{slash}G5_O3-Pad42)") (class "Default")
      (node (ref "U4") (pin "42") (pinfunction "PB6/TX1/I2C1_SCL/G5_O3_42") (pintype "passive"))
    )
    (net (code "112") (name "unconnected-(U4-PB7{slash}RX1{slash}I2C1_SDA{slash}G5_O4-Pad43)") (class "Default")
      (node (ref "U4") (pin "43") (pinfunction "PB7/RX1/I2C1_SDA/G5_O4_43") (pintype "passive"))
    )
    (net (code "113") (name "unconnected-(U4-PB12{slash}SPI2_NSS{slash}LPU1_DE{slash}G6_O2-Pad25)") (class "Default")
      (node (ref "U4") (pin "25") (pinfunction "PB12/SPI2_NSS/LPU1_DE/G6_O2_25") (pintype "passive"))
    )
    (net (code "114") (name "unconnected-(U4-PB13{slash}SPI2_SCK{slash}I2C2_SCL{slash}TIM21_CH1{slash}G6_O3-Pad26)") (class "Default")
      (node (ref "U4") (pin "26") (pinfunction "PB13/SPI2_SCK/I2C2_SCL/TIM21_CH1/G6_O3_26") (pintype "passive"))
    )
    (net (code "115") (name "unconnected-(U4-PB14{slash}SPI2_MISO{slash}I2S2_SDA{slash}TIM21_CH2{slash}G6_O4-Pad27)") (class "Default")
      (node (ref "U4") (pin "27") (pinfunction "PB14/SPI2_MISO/I2S2_SDA/TIM21_CH2/G6_O4_27") (pintype "passive"))
    )
    (net (code "116") (name "unconnected-(U4-PB15{slash}SPI2_MOSI-Pad28)") (class "Default")
      (node (ref "U4") (pin "28") (pinfunction "PB15/SPI2_MOSI_28") (pintype "passive"))
    )
  )
)
